# ProPrj_Ideal_Diode_2025-12-23.net
KiCad netlist of a schematic drawn in EasyEDA Pro
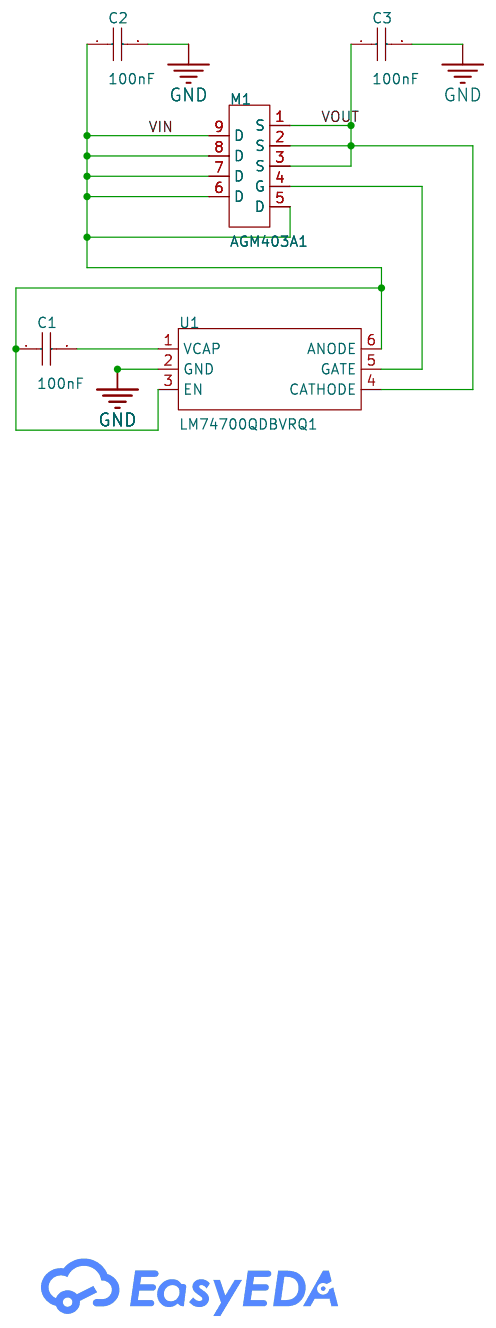
[diagram p0: schematic sheet]

(export (version "E")
  (design (tool "Eeschema 10.0.6"))
  (components
    (comp (ref "C1")
      (value "100nF")
      (footprint "easyedapro:C0402")
      (description "Capacitance:100nF Tolerance:±20% Tolerance:±20% Voltage Rating:50V Temperature Coefficient:Y5V")
      (fields (field (name "Manufacturer Part") "0402F104M500NT") (field (name "Manufacturer") "FH(风华)"))
      (libsource (lib "easyedapro") (part "0402F104M500NT"))
    )
    (comp (ref "C2")
      (value "100nF")
      (footprint "easyedapro:C0402")
      (description "Capacitance:100nF Tolerance:±20% Tolerance:±20% Voltage Rating:50V Temperature Coefficient:Y5V")
      (fields (field (name "Manufacturer Part") "0402F104M500NT") (field (name "Manufacturer") "FH(风华)"))
      (libsource (lib "easyedapro") (part "0402F104M500NT"))
    )
    (comp (ref "C3")
      (value "100nF")
      (footprint "easyedapro:C0402")
      (description "Capacitance:100nF Tolerance:±20% Tolerance:±20% Voltage Rating:50V Temperature Coefficient:Y5V")
      (fields (field (name "Manufacturer Part") "0402F104M500NT") (field (name "Manufacturer") "FH(风华)"))
      (libsource (lib "easyedapro") (part "0402F104M500NT"))
    )
    (comp (ref "M1")
      (value "AGM403A1")
      (footprint "easyedapro:DFN-8_L5.8-W4.9-P1.27-LS6.0-BL-1")
      (fields (field (name "Manufacturer") "AGMSEMI(芯控源)"))
      (libsource (lib "easyedapro") (part "AGM403A1"))
    )
    (comp (ref "U1")
      (value "LM74700QDBVRQ1")
      (footprint "easyedapro:SOT-23-6_L2.9-W1.6-P0.95-LS2.8-BL")
      (fields (field (name "Manufacturer") "TI(德州仪器)"))
      (libsource (lib "easyedapro") (part "LM74700QDBVRQ1"))
    )
  )
  (nets
    (net (code "1") (name "/VIN") (class "Default")
      (node (ref "C1") (pin "1") (pinfunction "1_1") (pintype "input"))
      (node (ref "C2") (pin "1") (pinfunction "1_1") (pintype "input"))
      (node (ref "M1") (pin "5") (pinfunction "D_5") (pintype "unspecified"))
      (node (ref "M1") (pin "6") (pinfunction "D_6") (pintype "unspecified"))
      (node (ref "M1") (pin "7") (pinfunction "D_7") (pintype "unspecified"))
      (node (ref "M1") (pin "8") (pinfunction "D_8") (pintype "unspecified"))
      (node (ref "M1") (pin "9") (pinfunction "D_9") (pintype "unspecified"))
      (node (ref "U1") (pin "3") (pinfunction "EN_3") (pintype "unspecified"))
      (node (ref "U1") (pin "6") (pinfunction "ANODE_6") (pintype "unspecified"))
    )
    (net (code "2") (name "/VOUT") (class "Default")
      (node (ref "C3") (pin "1") (pinfunction "1_1") (pintype "input"))
      (node (ref "M1") (pin "1") (pinfunction "S_1") (pintype "unspecified"))
      (node (ref "M1") (pin "2") (pinfunction "S_2") (pintype "unspecified"))
      (node (ref "M1") (pin "3") (pinfunction "S_3") (pintype "unspecified"))
      (node (ref "U1") (pin "4") (pinfunction "CATHODE_4") (pintype "unspecified"))
    )
    (net (code "3") (name "GND") (class "Default")
      (node (ref "C2") (pin "2") (pinfunction "2_2") (pintype "input"))
      (node (ref "C3") (pin "2") (pinfunction "2_2") (pintype "input"))
      (node (ref "U1") (pin "2") (pinfunction "GND_2") (pintype "unspecified"))
    )
    (net (code "4") (name "Net-(M1-G)") (class "Default")
      (node (ref "M1") (pin "4") (pinfunction "G_4") (pintype "unspecified"))
      (node (ref "U1") (pin "5") (pinfunction "GATE_5") (pintype "unspecified"))
    )
    (net (code "5") (name "Net-(U1-VCAP)") (class "Default")
      (node (ref "C1") (pin "2") (pinfunction "2_2") (pintype "input"))
      (node (ref "U1") (pin "1") (pinfunction "VCAP_1") (pintype "unspecified"))
    )
  )
)
